# R2_Power_Board.net
KiCad netlist of a schematic drawn in Altium Designer
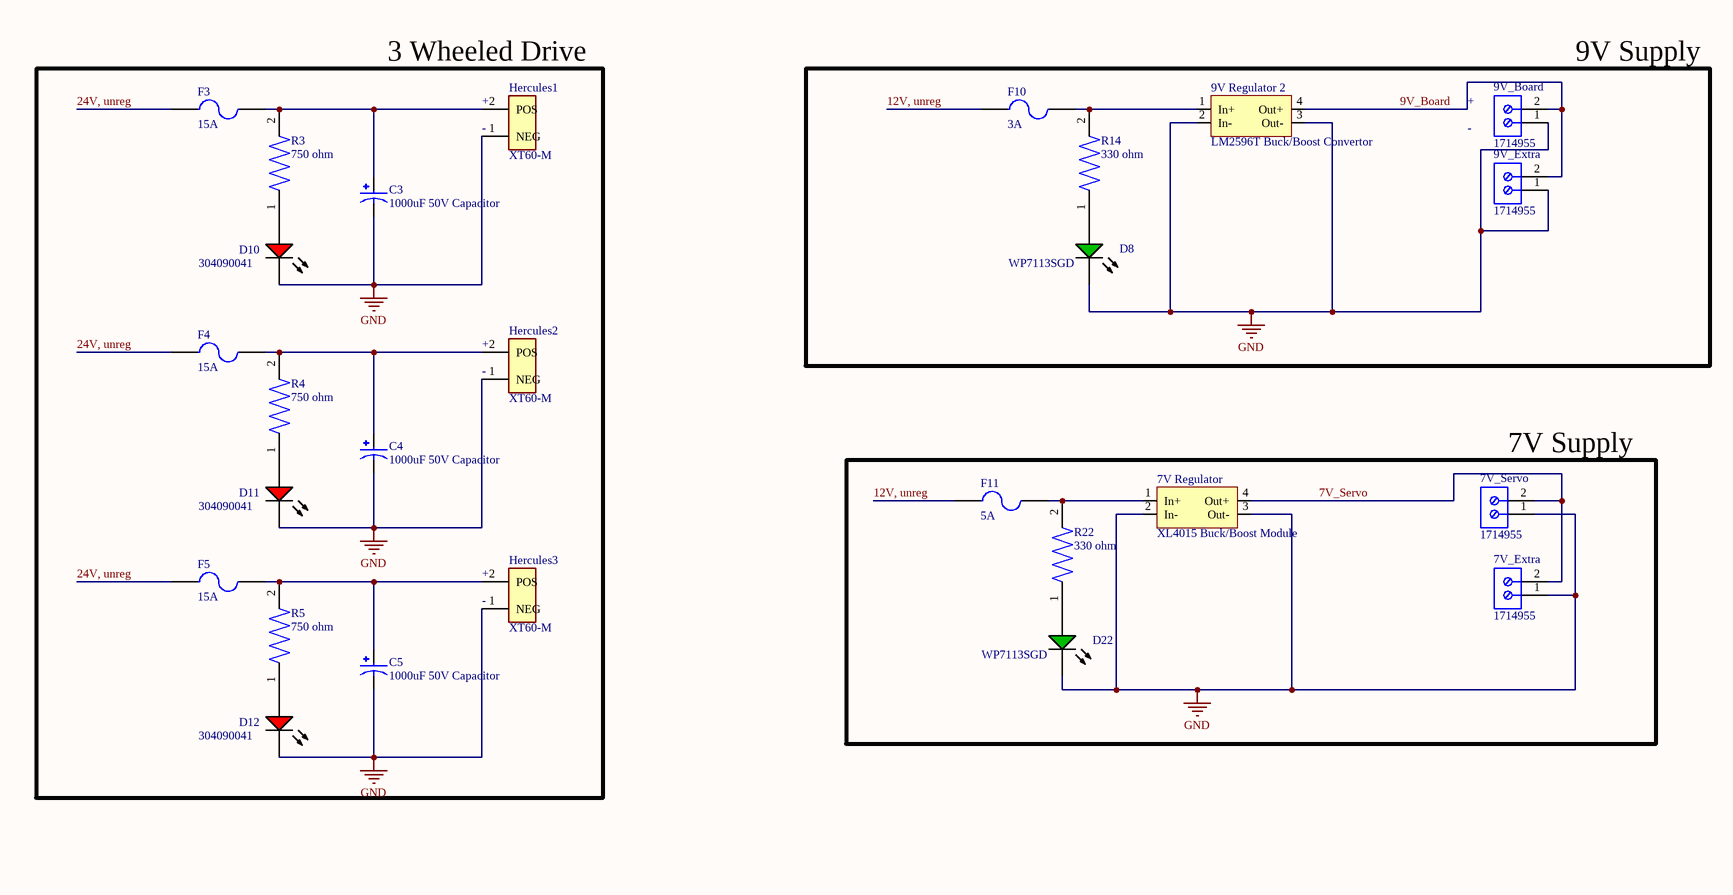
[diagram p0: R2_Power_Board.SchDoc, left]
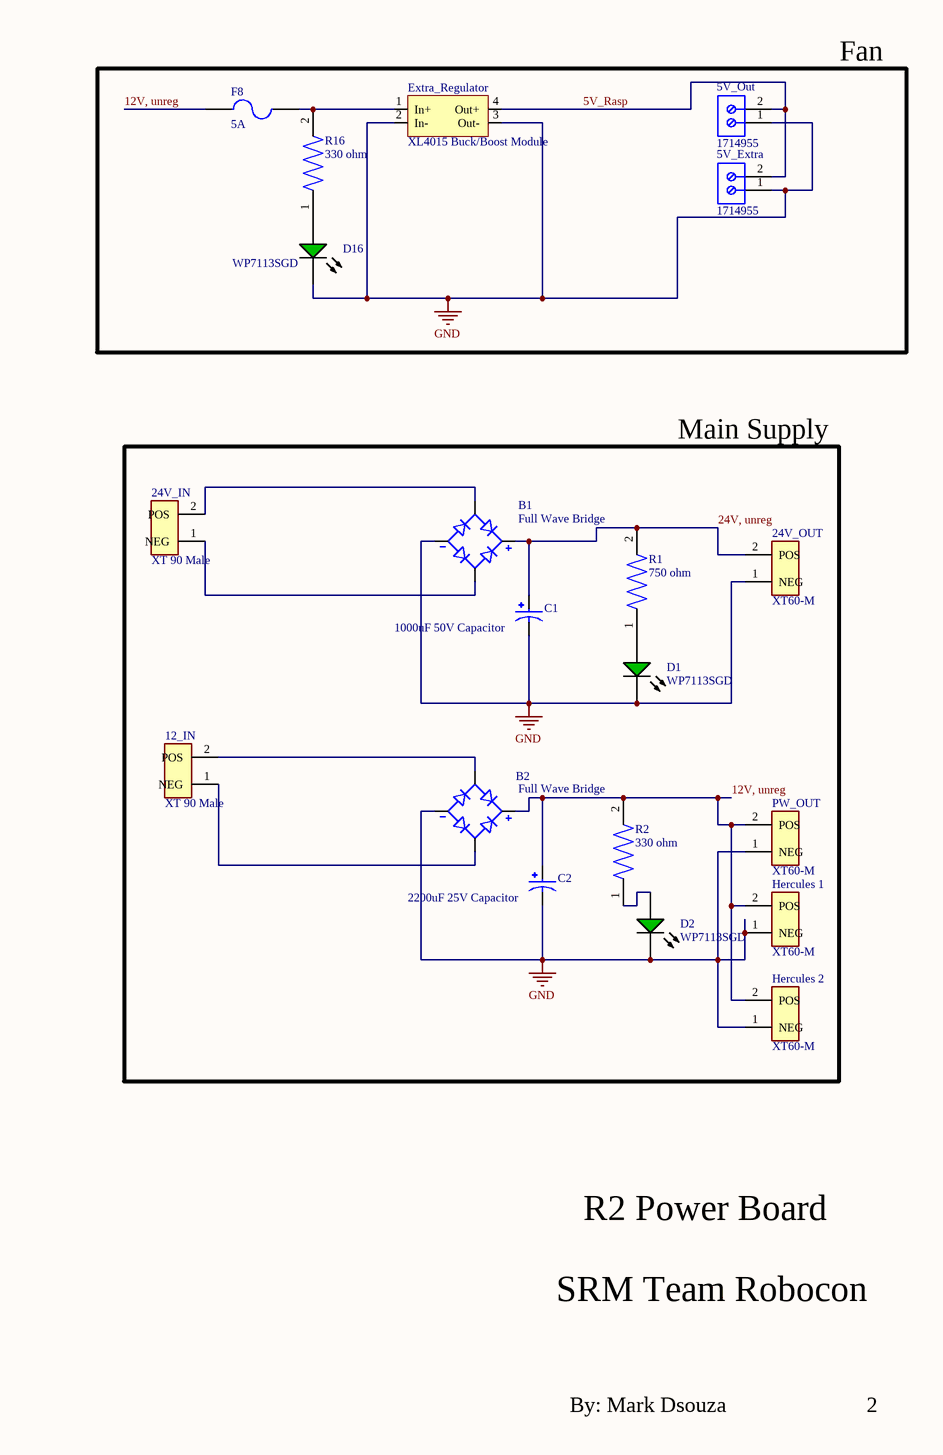
[diagram p1: R2_Power_Board.SchDoc, right]

(export (version "E")
  (design (tool "Eeschema 10.0.6"))
  (components
    (comp (ref "5V_Extra")
      (value "1714955")
      (footprint "6.35mm 2 Way Screw Terminal")
      (description "PC Terminal Block, Pitch 6.35 mm, 1 x 2 Position, Height 21.5 mm, Tail Lenght 5.1 mm, RoHS, Bulk")
      (fields (field (name "MANUFACTURER") "Phoenix Contact"))
      (libsource (lib "R2 BOT SCHLIB") (part "6.35mm 2 Way Screw Terminal"))
    )
    (comp (ref "5V_Out")
      (value "1714955")
      (footprint "6.35mm 2 Way Screw Terminal")
      (description "PC Terminal Block, Pitch 6.35 mm, 1 x 2 Position, Height 21.5 mm, Tail Lenght 5.1 mm, RoHS, Bulk")
      (fields (field (name "MANUFACTURER") "Phoenix Contact"))
      (libsource (lib "R2 BOT SCHLIB") (part "6.35mm 2 Way Screw Terminal"))
    )
    (comp (ref "7V Regulator")
      (value "XL4015 Buck/Boost Module")
      (footprint "XL4014 Module")
      (libsource (lib "R2 BOT SCHLIB") (part "XL4015 Buck/Boost Module"))
    )
    (comp (ref "7V_Extra")
      (value "1714955")
      (footprint "6.35mm 2 Way Screw Terminal")
      (description "PC Terminal Block, Pitch 6.35 mm, 1 x 2 Position, Height 21.5 mm, Tail Lenght 5.1 mm, RoHS, Bulk")
      (fields (field (name "MANUFACTURER") "Phoenix Contact"))
      (libsource (lib "R2 BOT SCHLIB") (part "6.35mm 2 Way Screw Terminal"))
    )
    (comp (ref "7V_Servo")
      (value "1714955")
      (footprint "6.35mm 2 Way Screw Terminal")
      (description "PC Terminal Block, Pitch 6.35 mm, 1 x 2 Position, Height 21.5 mm, Tail Lenght 5.1 mm, RoHS, Bulk")
      (fields (field (name "MANUFACTURER") "Phoenix Contact"))
      (libsource (lib "R2 BOT SCHLIB") (part "6.35mm 2 Way Screw Terminal"))
    )
    (comp (ref "9V Regulator 2")
      (value "LM2596T Buck/Boost Convertor")
      (footprint "LM2596 MODULE")
      (libsource (lib "R2 BOT SCHLIB") (part "LM2596T Buck/Boost Convertor"))
    )
    (comp (ref "9V_Board")
      (value "1714955")
      (footprint "6.35mm 2 Way Screw Terminal")
      (description "PC Terminal Block, Pitch 6.35 mm, 1 x 2 Position, Height 21.5 mm, Tail Lenght 5.1 mm, RoHS, Bulk")
      (fields (field (name "MANUFACTURER") "Phoenix Contact"))
      (libsource (lib "R2 BOT SCHLIB") (part "6.35mm 2 Way Screw Terminal"))
    )
    (comp (ref "9V_Extra")
      (value "1714955")
      (footprint "6.35mm 2 Way Screw Terminal")
      (description "PC Terminal Block, Pitch 6.35 mm, 1 x 2 Position, Height 21.5 mm, Tail Lenght 5.1 mm, RoHS, Bulk")
      (fields (field (name "MANUFACTURER") "Phoenix Contact"))
      (libsource (lib "R2 BOT SCHLIB") (part "6.35mm 2 Way Screw Terminal"))
    )
    (comp (ref "12_IN")
      (value "XT 90 Male")
      (footprint "XT 90-M")
      (libsource (lib "R2 BOT SCHLIB") (part "XT 90 Male"))
    )
    (comp (ref "24V_IN")
      (value "XT 90 Male")
      (footprint "XT 90-M")
      (libsource (lib "R2 BOT SCHLIB") (part "XT 90 Male"))
    )
    (comp (ref "24V_OUT")
      (value "XT60-M")
      (footprint "AMASS_XT60-M")
      (description "Plug; DC supply; XT60; male; PIN: 2; for cable; soldered; 30A; 500V")
      (fields (field (name "MF") "AMASS"))
      (libsource (lib "R2 BOT SCHLIB") (part "XT60-M"))
    )
    (comp (ref "B1")
      (value "Full Wave Bridge")
      (footprint "Full Wave Bridge")
      (description "Full Wave Diode Bridge")
      (fields (field (name "PUBLISHER") "Altium Limited"))
      (libsource (lib "R2 BOT SCHLIB") (part "Full Wave Bridge"))
    )
    (comp (ref "B2")
      (value "Full Wave Bridge")
      (footprint "Full Wave Bridge")
      (description "Full Wave Diode Bridge")
      (fields (field (name "PUBLISHER") "Altium Limited"))
      (libsource (lib "R2 BOT SCHLIB") (part "Full Wave Bridge"))
    )
    (comp (ref "C1")
      (value "1000uF 50V Capacitor")
      (footprint "1000uF 50V Capacitor")
      (description "CAP ALUM 1000UF 20% 50V RADIAL")
      (fields (field (name "MF") "Panasonic") (field (name "MP") "EEU-HD1H102B"))
      (libsource (lib "R2 BOT SCHLIB") (part "1000uF 50V Capacitor"))
    )
    (comp (ref "C2")
      (value "2200uF 25V Capacitor")
      (footprint "2200uF 25V Capacitor")
      (description "Aluminum Electrolytic Capacitors, TA-A Series, 2200uF +/- 20%, 25V, Radial lead type(16x31.5mm)")
      (fields (field (name "MF") "Panasonic") (field (name "MP") "EEUTA1E222"))
      (libsource (lib "R2 BOT SCHLIB") (part "2200uF 25V Capacitor"))
    )
    (comp (ref "C3")
      (value "1000uF 50V Capacitor")
      (footprint "1000uF 50V Capacitor")
      (description "CAP ALUM 1000UF 20% 50V RADIAL")
      (fields (field (name "MF") "Panasonic") (field (name "MP") "EEU-HD1H102B"))
      (libsource (lib "R2 BOT SCHLIB") (part "1000uF 50V Capacitor"))
    )
    (comp (ref "C4")
      (value "1000uF 50V Capacitor")
      (footprint "1000uF 50V Capacitor")
      (description "CAP ALUM 1000UF 20% 50V RADIAL")
      (fields (field (name "MF") "Panasonic") (field (name "MP") "EEU-HD1H102B"))
      (libsource (lib "R2 BOT SCHLIB") (part "1000uF 50V Capacitor"))
    )
    (comp (ref "C5")
      (value "1000uF 50V Capacitor")
      (footprint "1000uF 50V Capacitor")
      (description "CAP ALUM 1000UF 20% 50V RADIAL")
      (fields (field (name "MF") "Panasonic") (field (name "MP") "EEU-HD1H102B"))
      (libsource (lib "R2 BOT SCHLIB") (part "1000uF 50V Capacitor"))
    )
    (comp (ref "D1")
      (value "WP7113SGD")
      (footprint "KING-WP7113SGD_V")
      (description "LED Green, 62.5 mW, 25 mA, -40 to 85 degC, 2-Pin THD, RoHS, Bulk")
      (fields (field (name "POWER") "62.5mW") (field (name "MANUFACTURER") "Kingbright"))
      (libsource (lib "ROBOCON 2022") (part "LED-GREEN-AK-2"))
    )
    (comp (ref "D2")
      (value "WP7113SGD")
      (footprint "KING-WP7113SGD_V")
      (description "LED Green, 62.5 mW, 25 mA, -40 to 85 degC, 2-Pin THD, RoHS, Bulk")
      (fields (field (name "POWER") "62.5mW") (field (name "MANUFACTURER") "Kingbright"))
      (libsource (lib "ROBOCON 2022") (part "LED-GREEN-AK-2"))
    )
    (comp (ref "D8")
      (value "WP7113SGD")
      (footprint "KING-WP7113SGD_V")
      (description "LED Green, 62.5 mW, 25 mA, -40 to 85 degC, 2-Pin THD, RoHS, Bulk")
      (fields (field (name "POWER") "62.5mW") (field (name "MANUFACTURER") "Kingbright"))
      (libsource (lib "ROBOCON 2022") (part "LED-GREEN-AK-2"))
    )
    (comp (ref "D10")
      (value "304090041")
      (footprint "LED-2P-2.28-3MM_A")
      (description "Red LED, 80 mW, 30 mA, -25 to 85 degC, 2-Pin THD")
      (fields (field (name "MANUFACTURER") "Shenzhen CGX"))
      (libsource (lib "ROBOCON 2022") (part "LED-RED-AK-2"))
    )
    (comp (ref "D11")
      (value "304090041")
      (footprint "LED-2P-2.28-3MM_A")
      (description "Red LED, 80 mW, 30 mA, -25 to 85 degC, 2-Pin THD")
      (fields (field (name "MANUFACTURER") "Shenzhen CGX"))
      (libsource (lib "ROBOCON 2022") (part "LED-RED-AK-2"))
    )
    (comp (ref "D12")
      (value "304090041")
      (footprint "LED-2P-2.28-3MM_A")
      (description "Red LED, 80 mW, 30 mA, -25 to 85 degC, 2-Pin THD")
      (fields (field (name "MANUFACTURER") "Shenzhen CGX"))
      (libsource (lib "ROBOCON 2022") (part "LED-RED-AK-2"))
    )
    (comp (ref "D16")
      (value "WP7113SGD")
      (footprint "KING-WP7113SGD_V")
      (description "LED Green, 62.5 mW, 25 mA, -40 to 85 degC, 2-Pin THD, RoHS, Bulk")
      (fields (field (name "POWER") "62.5mW") (field (name "MANUFACTURER") "Kingbright"))
      (libsource (lib "ROBOCON 2022") (part "LED-GREEN-AK-2"))
    )
    (comp (ref "D22")
      (value "WP7113SGD")
      (footprint "KING-WP7113SGD_V")
      (description "LED Green, 62.5 mW, 25 mA, -40 to 85 degC, 2-Pin THD, RoHS, Bulk")
      (fields (field (name "POWER") "62.5mW") (field (name "MANUFACTURER") "Kingbright"))
      (libsource (lib "ROBOCON 2022") (part "LED-GREEN-AK-2"))
    )
    (comp (ref "Extra_Regulator")
      (value "XL4015 Buck/Boost Module")
      (footprint "XL4014 Module")
      (libsource (lib "R2 BOT SCHLIB") (part "XL4015 Buck/Boost Module"))
    )
    (comp (ref "F3") (value "15A") (footprint "FUSE") (libsource (lib "R2 BOT SCHLIB") (part "Fuse")))
    (comp (ref "F4") (value "15A") (footprint "FUSE") (libsource (lib "R2 BOT SCHLIB") (part "Fuse")))
    (comp (ref "F5") (value "15A") (footprint "FUSE") (libsource (lib "R2 BOT SCHLIB") (part "Fuse")))
    (comp (ref "F8")
      (value "5A")
      (footprint "Fuse_small")
      (libsource (lib "R2 BOT SCHLIB") (part "Fuse _small"))
    )
    (comp (ref "F10")
      (value "3A")
      (footprint "Fuse_small")
      (libsource (lib "R2 BOT SCHLIB") (part "Fuse _small"))
    )
    (comp (ref "F11")
      (value "5A")
      (footprint "Fuse_small")
      (libsource (lib "R2 BOT SCHLIB") (part "Fuse _small"))
    )
    (comp (ref "Hercules 1")
      (value "XT60-M")
      (footprint "AMASS_XT60-M")
      (description "Plug; DC supply; XT60; male; PIN: 2; for cable; soldered; 30A; 500V")
      (fields (field (name "MF") "AMASS"))
      (libsource (lib "R2 BOT SCHLIB") (part "XT60-M"))
    )
    (comp (ref "Hercules 2")
      (value "XT60-M")
      (footprint "AMASS_XT60-M")
      (description "Plug; DC supply; XT60; male; PIN: 2; for cable; soldered; 30A; 500V")
      (fields (field (name "MF") "AMASS"))
      (libsource (lib "R2 BOT SCHLIB") (part "XT60-M"))
    )
    (comp (ref "Hercules1")
      (value "XT60-M")
      (footprint "AMASS_XT60-M")
      (description "Plug; DC supply; XT60; male; PIN: 2; for cable; soldered; 30A; 500V")
      (fields (field (name "MF") "AMASS"))
      (libsource (lib "R2 BOT SCHLIB") (part "XT60-M"))
    )
    (comp (ref "Hercules2")
      (value "XT60-M")
      (footprint "AMASS_XT60-M")
      (description "Plug; DC supply; XT60; male; PIN: 2; for cable; soldered; 30A; 500V")
      (fields (field (name "MF") "AMASS"))
      (libsource (lib "R2 BOT SCHLIB") (part "XT60-M"))
    )
    (comp (ref "Hercules3")
      (value "XT60-M")
      (footprint "AMASS_XT60-M")
      (description "Plug; DC supply; XT60; male; PIN: 2; for cable; soldered; 30A; 500V")
      (fields (field (name "MF") "AMASS"))
      (libsource (lib "R2 BOT SCHLIB") (part "XT60-M"))
    )
    (comp (ref "PW_OUT")
      (value "XT60-M")
      (footprint "AMASS_XT60-M")
      (description "Plug; DC supply; XT60; male; PIN: 2; for cable; soldered; 30A; 500V")
      (fields (field (name "MF") "AMASS"))
      (libsource (lib "R2 BOT SCHLIB") (part "XT60-M"))
    )
    (comp (ref "R1")
      (value "750 ohm")
      (footprint "TH Resistor")
      (description "1 MOhms Â±5% 0.25W, 1/4W Through Hole Resistor Axial - Carbon Film")
      (fields (field (name "MF") "TE Connectivity") (field (name "MP") "3-1623927-1"))
      (libsource (lib "R2 BOT SCHLIB") (part "TH Resistor"))
    )
    (comp (ref "R2")
      (value "330 ohm")
      (footprint "TH Resistor")
      (description "1 MOhms Â±5% 0.25W, 1/4W Through Hole Resistor Axial - Carbon Film")
      (fields (field (name "MF") "TE Connectivity") (field (name "MP") "3-1623927-1"))
      (libsource (lib "R2 BOT SCHLIB") (part "TH Resistor"))
    )
    (comp (ref "R3")
      (value "750 ohm")
      (footprint "TH Resistor")
      (description "1 MOhms Â±5% 0.25W, 1/4W Through Hole Resistor Axial - Carbon Film")
      (fields (field (name "MF") "TE Connectivity") (field (name "MP") "3-1623927-1"))
      (libsource (lib "R2 BOT SCHLIB") (part "TH Resistor"))
    )
    (comp (ref "R4")
      (value "750 ohm")
      (footprint "TH Resistor")
      (description "1 MOhms Â±5% 0.25W, 1/4W Through Hole Resistor Axial - Carbon Film")
      (fields (field (name "MF") "TE Connectivity") (field (name "MP") "3-1623927-1"))
      (libsource (lib "R2 BOT SCHLIB") (part "TH Resistor"))
    )
    (comp (ref "R5")
      (value "750 ohm")
      (footprint "TH Resistor")
      (description "1 MOhms Â±5% 0.25W, 1/4W Through Hole Resistor Axial - Carbon Film")
      (fields (field (name "MF") "TE Connectivity") (field (name "MP") "3-1623927-1"))
      (libsource (lib "R2 BOT SCHLIB") (part "TH Resistor"))
    )
    (comp (ref "R14")
      (value "330 ohm")
      (footprint "TH Resistor")
      (description "1 MOhms Â±5% 0.25W, 1/4W Through Hole Resistor Axial - Carbon Film")
      (fields (field (name "MF") "TE Connectivity") (field (name "MP") "3-1623927-1"))
      (libsource (lib "R2 BOT SCHLIB") (part "TH Resistor"))
    )
    (comp (ref "R16")
      (value "330 ohm")
      (footprint "TH Resistor")
      (description "1 MOhms Â±5% 0.25W, 1/4W Through Hole Resistor Axial - Carbon Film")
      (fields (field (name "MF") "TE Connectivity") (field (name "MP") "3-1623927-1"))
      (libsource (lib "R2 BOT SCHLIB") (part "TH Resistor"))
    )
    (comp (ref "R22")
      (value "330 ohm")
      (footprint "TH Resistor")
      (description "1 MOhms Â±5% 0.25W, 1/4W Through Hole Resistor Axial - Carbon Film")
      (fields (field (name "MF") "TE Connectivity") (field (name "MP") "3-1623927-1"))
      (libsource (lib "R2 BOT SCHLIB") (part "TH Resistor"))
    )
  )
  (nets
    (net (code "1") (name "/5V_Rasp") (class "Default")
      (node (ref "5V_Extra") (pin "2") (pinfunction "2_2") (pintype "passive"))
      (node (ref "5V_Out") (pin "2") (pinfunction "2_2") (pintype "passive"))
      (node (ref "Extra_Regulator") (pin "4") (pinfunction "Out+_4") (pintype "power_in"))
    )
    (net (code "2") (name "/7V_Servo") (class "Default")
      (node (ref "7V Regulator") (pin "4") (pinfunction "Out+_4") (pintype "power_in"))
      (node (ref "7V_Extra") (pin "2") (pinfunction "2_2") (pintype "passive"))
      (node (ref "7V_Servo") (pin "2") (pinfunction "2_2") (pintype "passive"))
    )
    (net (code "3") (name "/9V_Board") (class "Default")
      (node (ref "9V Regulator 2") (pin "4") (pinfunction "Out+_4") (pintype "power_in"))
      (node (ref "9V_Board") (pin "2") (pinfunction "2_2") (pintype "passive"))
      (node (ref "9V_Extra") (pin "2") (pinfunction "2_2") (pintype "passive"))
    )
    (net (code "4") (name "/12V, unreg") (class "Default")
      (node (ref "B2") (pin "P") (pinfunction "P_P") (pintype "passive"))
      (node (ref "C2") (pin "P") (pinfunction "P_P") (pintype "passive"))
      (node (ref "F10") (pin "1") (pinfunction "1_1") (pintype "passive"))
      (node (ref "F11") (pin "1") (pinfunction "1_1") (pintype "passive"))
      (node (ref "F8") (pin "1") (pinfunction "1_1") (pintype "passive"))
      (node (ref "Hercules 1") (pin "2") (pinfunction "POS_2") (pintype "passive"))
      (node (ref "Hercules 2") (pin "2") (pinfunction "POS_2") (pintype "passive"))
      (node (ref "PW_OUT") (pin "2") (pinfunction "POS_2") (pintype "passive"))
      (node (ref "R2") (pin "2") (pinfunction "2_2") (pintype "passive"))
    )
    (net (code "5") (name "/24V, unreg") (class "Default")
      (node (ref "24V_OUT") (pin "2") (pinfunction "POS_2") (pintype "passive"))
      (node (ref "B1") (pin "P") (pinfunction "P_P") (pintype "passive"))
      (node (ref "C1") (pin "P") (pinfunction "P_P") (pintype "passive"))
      (node (ref "F3") (pin "1") (pinfunction "1_1") (pintype "passive"))
      (node (ref "F4") (pin "1") (pinfunction "1_1") (pintype "passive"))
      (node (ref "F5") (pin "1") (pinfunction "1_1") (pintype "passive"))
      (node (ref "R1") (pin "2") (pinfunction "2_2") (pintype "passive"))
    )
    (net (code "6") (name "GND") (class "Default")
      (node (ref "24V_OUT") (pin "1") (pinfunction "NEG_1") (pintype "passive"))
      (node (ref "5V_Extra") (pin "1") (pinfunction "1_1") (pintype "passive"))
      (node (ref "5V_Out") (pin "1") (pinfunction "1_1") (pintype "passive"))
      (node (ref "7V Regulator") (pin "2") (pinfunction "In-_2") (pintype "power_in"))
      (node (ref "7V Regulator") (pin "3") (pinfunction "Out-_3") (pintype "power_in"))
      (node (ref "7V_Extra") (pin "1") (pinfunction "1_1") (pintype "passive"))
      (node (ref "7V_Servo") (pin "1") (pinfunction "1_1") (pintype "passive"))
      (node (ref "9V Regulator 2") (pin "2") (pinfunction "In-_2") (pintype "power_in"))
      (node (ref "9V Regulator 2") (pin "3") (pinfunction "Out-_3") (pintype "power_in"))
      (node (ref "9V_Board") (pin "1") (pinfunction "1_1") (pintype "passive"))
      (node (ref "9V_Extra") (pin "1") (pinfunction "1_1") (pintype "passive"))
      (node (ref "B1") (pin "N") (pinfunction "N_N") (pintype "passive"))
      (node (ref "B2") (pin "N") (pinfunction "N_N") (pintype "passive"))
      (node (ref "C1") (pin "N") (pinfunction "N_N") (pintype "passive"))
      (node (ref "C2") (pin "N") (pinfunction "N_N") (pintype "passive"))
      (node (ref "C3") (pin "N") (pinfunction "N_N") (pintype "passive"))
      (node (ref "C4") (pin "N") (pinfunction "N_N") (pintype "passive"))
      (node (ref "C5") (pin "N") (pinfunction "N_N") (pintype "passive"))
      (node (ref "D1") (pin "2") (pinfunction "K_2") (pintype "passive"))
      (node (ref "D10") (pin "2") (pinfunction "K_2") (pintype "passive"))
      (node (ref "D11") (pin "2") (pinfunction "K_2") (pintype "passive"))
      (node (ref "D12") (pin "2") (pinfunction "K_2") (pintype "passive"))
      (node (ref "D16") (pin "2") (pinfunction "K_2") (pintype "passive"))
      (node (ref "D2") (pin "2") (pinfunction "K_2") (pintype "passive"))
      (node (ref "D22") (pin "2") (pinfunction "K_2") (pintype "passive"))
      (node (ref "D8") (pin "2") (pinfunction "K_2") (pintype "passive"))
      (node (ref "Extra_Regulator") (pin "2") (pinfunction "In-_2") (pintype "power_in"))
      (node (ref "Extra_Regulator") (pin "3") (pinfunction "Out-_3") (pintype "power_in"))
      (node (ref "Hercules 1") (pin "1") (pinfunction "NEG_1") (pintype "passive"))
      (node (ref "Hercules 2") (pin "1") (pinfunction "NEG_1") (pintype "passive"))
      (node (ref "Hercules1") (pin "1") (pinfunction "NEG_1") (pintype "passive"))
      (node (ref "Hercules2") (pin "1") (pinfunction "NEG_1") (pintype "passive"))
      (node (ref "Hercules3") (pin "1") (pinfunction "NEG_1") (pintype "passive"))
      (node (ref "PW_OUT") (pin "1") (pinfunction "NEG_1") (pintype "passive"))
    )
    (net (code "7") (name "Net-(7V Regulator-In+)") (class "Default")
      (node (ref "7V Regulator") (pin "1") (pinfunction "In+_1") (pintype "power_in"))
      (node (ref "F11") (pin "2") (pinfunction "2_2") (pintype "passive"))
      (node (ref "R22") (pin "2") (pinfunction "2_2") (pintype "passive"))
    )
    (net (code "8") (name "Net-(9V Regulator 2-In+)") (class "Default")
      (node (ref "9V Regulator 2") (pin "1") (pinfunction "In+_1") (pintype "power_in"))
      (node (ref "F10") (pin "2") (pinfunction "2_2") (pintype "passive"))
      (node (ref "R14") (pin "2") (pinfunction "2_2") (pintype "passive"))
    )
    (net (code "9") (name "Net-(12_IN-NEG)") (class "Default")
      (node (ref "12_IN") (pin "1") (pinfunction "NEG_1") (pintype "passive"))
      (node (ref "B2") (pin "AC1") (pinfunction "AC1_AC1") (pintype "passive"))
    )
    (net (code "10") (name "Net-(12_IN-POS)") (class "Default")
      (node (ref "12_IN") (pin "2") (pinfunction "POS_2") (pintype "passive"))
      (node (ref "B2") (pin "AC2") (pinfunction "AC2_AC2") (pintype "passive"))
    )
    (net (code "11") (name "Net-(24V_IN-NEG)") (class "Default")
      (node (ref "24V_IN") (pin "1") (pinfunction "NEG_1") (pintype "passive"))
      (node (ref "B1") (pin "AC1") (pinfunction "AC1_AC1") (pintype "passive"))
    )
    (net (code "12") (name "Net-(24V_IN-POS)") (class "Default")
      (node (ref "24V_IN") (pin "2") (pinfunction "POS_2") (pintype "passive"))
      (node (ref "B1") (pin "AC2") (pinfunction "AC2_AC2") (pintype "passive"))
    )
    (net (code "13") (name "Net-(D1-A)") (class "Default")
      (node (ref "D1") (pin "1") (pinfunction "A_1") (pintype "passive"))
      (node (ref "R1") (pin "1") (pinfunction "1_1") (pintype "passive"))
    )
    (net (code "14") (name "Net-(D2-A)") (class "Default")
      (node (ref "D2") (pin "1") (pinfunction "A_1") (pintype "passive"))
      (node (ref "R2") (pin "1") (pinfunction "1_1") (pintype "passive"))
    )
    (net (code "15") (name "Net-(D8-A)") (class "Default")
      (node (ref "D8") (pin "1") (pinfunction "A_1") (pintype "passive"))
      (node (ref "R14") (pin "1") (pinfunction "1_1") (pintype "passive"))
    )
    (net (code "16") (name "Net-(D10-A)") (class "Default")
      (node (ref "D10") (pin "1") (pinfunction "A_1") (pintype "passive"))
      (node (ref "R3") (pin "1") (pinfunction "1_1") (pintype "passive"))
    )
    (net (code "17") (name "Net-(D11-A)") (class "Default")
      (node (ref "D11") (pin "1") (pinfunction "A_1") (pintype "passive"))
      (node (ref "R4") (pin "1") (pinfunction "1_1") (pintype "passive"))
    )
    (net (code "18") (name "Net-(D12-A)") (class "Default")
      (node (ref "D12") (pin "1") (pinfunction "A_1") (pintype "passive"))
      (node (ref "R5") (pin "1") (pinfunction "1_1") (pintype "passive"))
    )
    (net (code "19") (name "Net-(D16-A)") (class "Default")
      (node (ref "D16") (pin "1") (pinfunction "A_1") (pintype "passive"))
      (node (ref "R16") (pin "1") (pinfunction "1_1") (pintype "passive"))
    )
    (net (code "20") (name "Net-(D22-A)") (class "Default")
      (node (ref "D22") (pin "1") (pinfunction "A_1") (pintype "passive"))
      (node (ref "R22") (pin "1") (pinfunction "1_1") (pintype "passive"))
    )
    (net (code "21") (name "Net-(Extra_Regulator-In+)") (class "Default")
      (node (ref "Extra_Regulator") (pin "1") (pinfunction "In+_1") (pintype "power_in"))
      (node (ref "F8") (pin "2") (pinfunction "2_2") (pintype "passive"))
      (node (ref "R16") (pin "2") (pinfunction "2_2") (pintype "passive"))
    )
    (net (code "22") (name "Net-(Hercules1-POS)") (class "Default")
      (node (ref "C3") (pin "P") (pinfunction "P_P") (pintype "passive"))
      (node (ref "F3") (pin "2") (pinfunction "2_2") (pintype "passive"))
      (node (ref "Hercules1") (pin "2") (pinfunction "POS_2") (pintype "passive"))
      (node (ref "R3") (pin "2") (pinfunction "2_2") (pintype "passive"))
    )
    (net (code "23") (name "Net-(Hercules2-POS)") (class "Default")
      (node (ref "C4") (pin "P") (pinfunction "P_P") (pintype "passive"))
      (node (ref "F4") (pin "2") (pinfunction "2_2") (pintype "passive"))
      (node (ref "Hercules2") (pin "2") (pinfunction "POS_2") (pintype "passive"))
      (node (ref "R4") (pin "2") (pinfunction "2_2") (pintype "passive"))
    )
    (net (code "24") (name "Net-(Hercules3-POS)") (class "Default")
      (node (ref "C5") (pin "P") (pinfunction "P_P") (pintype "passive"))
      (node (ref "F5") (pin "2") (pinfunction "2_2") (pintype "passive"))
      (node (ref "Hercules3") (pin "2") (pinfunction "POS_2") (pintype "passive"))
      (node (ref "R5") (pin "2") (pinfunction "2_2") (pintype "passive"))
    )
  )
)
